# 08-3V3_Monitor.net
KiCad netlist of a schematic drawn in Altium Designer
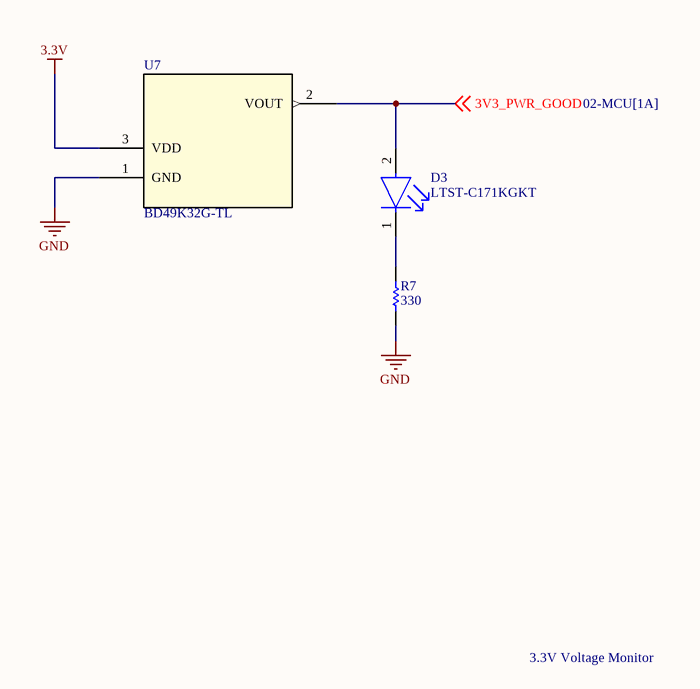
[diagram p0: 08-3V3_Monitor.SchDoc]

(export (version "E")
  (design (tool "Eeschema 10.0.6"))
  (components
    (comp (ref "D3")
      (value "LTST-C171KGKT")
      (footprint "FP-LTST-C171KGKT-MFG")
      (description "LED GREEN CLEAR SMD")
      (libsource (lib "Altium Content Vault") (part "8706943c75ba83719d021d2fdc84c58"))
    )
    (comp (ref "R7")
      (value "330")
      (footprint "RES_0805")
      (description "RES 330 OHM 1% 1/8W 0805")
      (fields (field (name "TOLERANCE") "1%"))
      (libsource (lib "team6") (part "RES_0805_R_330.00"))
    )
    (comp (ref "U7")
      (value "BD49K32G-TL")
      (footprint "SSOP3_ROM")
      (description "No Description Available")
      (fields (field (name "COPYRIGHT") "Copyright (C) 2022 Ultra Librarian. All rights reserved."))
      (libsource (lib "team6") (part "BD49K32G-TL"))
    )
  )
  (nets
    (net (code "1") (name "3.3V") (class "Default")
      (node (ref "U7") (pin "3") (pinfunction "VDD_3") (pintype "power_in"))
    )
    (net (code "2") (name "3V3_PWR_GOOD") (class "Default")
      (node (ref "D3") (pin "2") (pinfunction "A_2") (pintype "passive"))
      (node (ref "U7") (pin "2") (pinfunction "VOUT_2") (pintype "output"))
    )
    (net (code "3") (name "GND") (class "Default")
      (node (ref "R7") (pin "1") (pinfunction "1_1") (pintype "passive"))
      (node (ref "U7") (pin "1") (pinfunction "GND_1") (pintype "passive"))
    )
    (net (code "4") (name "Net-(D3-C)") (class "Default")
      (node (ref "D3") (pin "1") (pinfunction "C_1") (pintype "passive"))
      (node (ref "R7") (pin "2") (pinfunction "2_2") (pintype "passive"))
    )
  )
)
